# breakout-1.net
KiCad netlist of a schematic drawn in Altium Designer
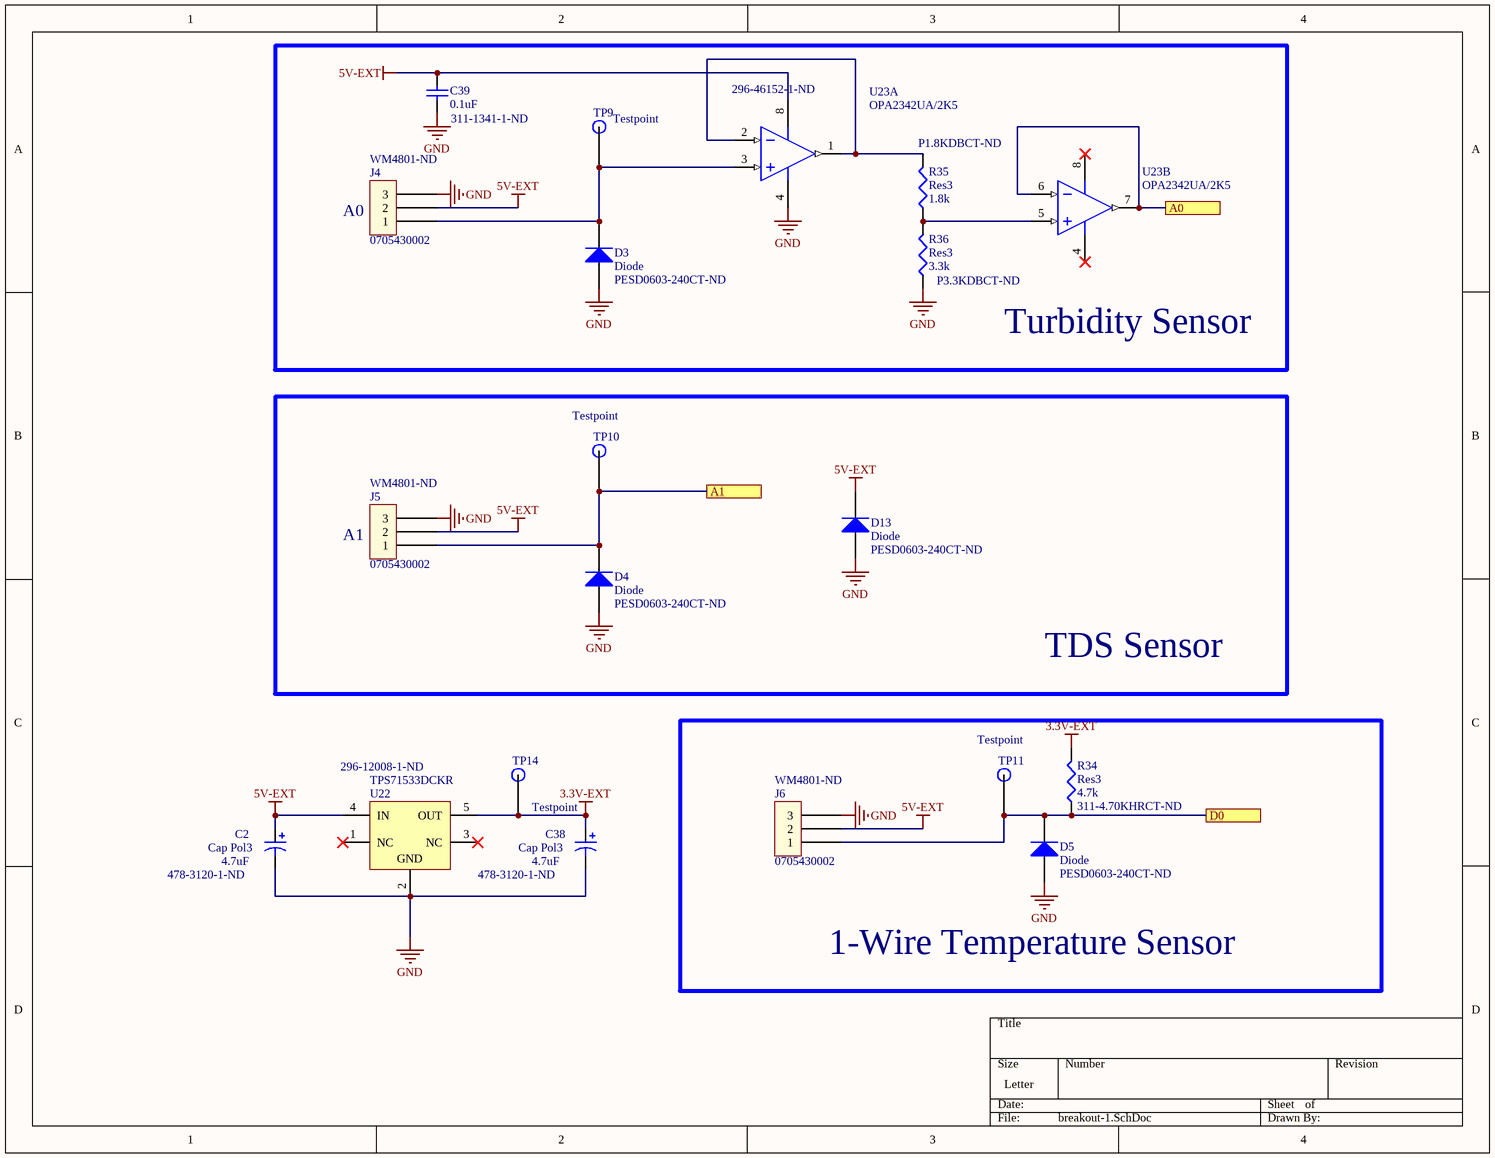
[diagram p0: breakout-1.SchDoc]

(export (version "E")
  (design (tool "Eeschema 10.0.6"))
  (components
    (comp (ref "C2")
      (value "Cap Pol3")
      (footprint "1206-pol")
      (description "Polarized Capacitor (Surface Mount)")
      (fields
        (field (name "ALTIUM_VALUE") "4.7uF")
        (field (name "SUPPLIER PART NUMBER 1") "478-3120-1-ND")
        (field (name "MANUFACTURER") "AVX Corporation")
        (field (name "MANUFACTURER PART NUMBER") "NOJA475M010RWJ")
      )
      (libsource (lib "Miscellaneous Devices") (part "Cap Pol3"))
    )
    (comp (ref "C38")
      (value "Cap Pol3")
      (footprint "1206-pol")
      (description "Polarized Capacitor (Surface Mount)")
      (fields
        (field (name "ALTIUM_VALUE") "4.7uF")
        (field (name "SUPPLIER PART NUMBER 1") "478-3120-1-ND")
        (field (name "MANUFACTURER") "AVX Corporation")
        (field (name "MANUFACTURER PART NUMBER") "NOJA475M010RWJ")
      )
      (libsource (lib "Miscellaneous Devices") (part "Cap Pol3"))
    )
    (comp (ref "C39")
      (value "0.1uF")
      (footprint "1608[0603]")
      (description "Capacitor (Semiconductor SIM Model)")
      (fields
        (field (name "SUPPLIER PART NUMBER 1") "311-1341-1-ND")
        (field (name "MANUFACTURER") "Yageo")
        (field (name "MANUFACTURER PART NUMBER") "CC0603KRX7R8BB104")
      )
      (libsource (lib "Miscellaneous Devices") (part "Cap Semi"))
    )
    (comp (ref "D3")
      (value "Diode")
      (footprint "J1-0603")
      (description "Default Diode")
      (fields
        (field (name "SUPPLIER PART NUMBER 1") "PESD0603-240CT-ND")
        (field (name "MANUFACTURER") "Littelfuse")
        (field (name "MANUFACTURER PART NUMBER") "RF1256-000")
        (field (name "PUBLISHER") "Altium Limited")
      )
      (libsource (lib "Miscellaneous Devices") (part "Diode"))
    )
    (comp (ref "D4")
      (value "Diode")
      (footprint "J1-0603")
      (description "Default Diode")
      (fields
        (field (name "SUPPLIER PART NUMBER 1") "PESD0603-240CT-ND")
        (field (name "MANUFACTURER") "Littelfuse")
        (field (name "MANUFACTURER PART NUMBER") "RF1256-000")
        (field (name "PUBLISHER") "Altium Limited")
      )
      (libsource (lib "Miscellaneous Devices") (part "Diode"))
    )
    (comp (ref "D5")
      (value "Diode")
      (footprint "J1-0603")
      (description "Default Diode")
      (fields
        (field (name "SUPPLIER PART NUMBER 1") "PESD0603-240CT-ND")
        (field (name "MANUFACTURER") "Littelfuse")
        (field (name "MANUFACTURER PART NUMBER") "RF1256-000")
        (field (name "PUBLISHER") "Altium Limited")
      )
      (libsource (lib "Miscellaneous Devices") (part "Diode"))
    )
    (comp (ref "D13")
      (value "Diode")
      (footprint "J1-0603")
      (description "Default Diode")
      (fields
        (field (name "SUPPLIER PART NUMBER 1") "PESD0603-240CT-ND")
        (field (name "MANUFACTURER") "Littelfuse")
        (field (name "MANUFACTURER PART NUMBER") "RF1256-000")
        (field (name "PUBLISHER") "Altium Limited")
      )
      (libsource (lib "Miscellaneous Devices") (part "Diode"))
    )
    (comp (ref "J4")
      (value "0705430002")
      (footprint "0705430002")
      (fields
        (field (name "SUPPLIER PART NUMBER 1") "WM4801-ND")
        (field (name "MANUFACTURER") "Molex")
        (field (name "MANUFACTURER PART NUMBER") "70543-0002")
      )
      (libsource (lib "molex") (part "0705430002"))
    )
    (comp (ref "J5")
      (value "0705430002")
      (footprint "0705430002")
      (fields
        (field (name "SUPPLIER PART NUMBER 1") "WM4801-ND")
        (field (name "MANUFACTURER") "Molex")
        (field (name "MANUFACTURER PART NUMBER") "70543-0002")
      )
      (libsource (lib "molex") (part "0705430002"))
    )
    (comp (ref "J6")
      (value "0705430002")
      (footprint "0705430002")
      (fields
        (field (name "SUPPLIER PART NUMBER 1") "WM4801-ND")
        (field (name "MANUFACTURER") "Molex")
        (field (name "MANUFACTURER PART NUMBER") "70543-0002")
      )
      (libsource (lib "molex") (part "0705430002"))
    )
    (comp (ref "R34")
      (value "Res3")
      (footprint "J1-0603")
      (description "Resistor")
      (fields
        (field (name "ALTIUM_VALUE") "4.7k")
        (field (name "SUPPLIER PART NUMBER 1") "311-4.70KHRCT-ND")
        (field (name "MANUFACTURER") "Yageo")
        (field (name "MANUFACTURER PART NUMBER") "RC0603FR-074K7L")
        (field (name "PUBLISHER") "Altium Limited")
      )
      (libsource (lib "Miscellaneous Devices") (part "Res3"))
    )
    (comp (ref "R35")
      (value "Res3")
      (footprint "J1-0603")
      (description "Resistor")
      (fields
        (field (name "ALTIUM_VALUE") "1.8k")
        (field (name "SUPPLIER PART NUMBER 1") "P1.8KDBCT-ND")
        (field (name "MANUFACTURER") "Panasonic")
        (field (name "MANUFACTURER PART NUMBER") "ERA3AEB182V")
        (field (name "PUBLISHER") "Altium Limited")
      )
      (libsource (lib "Miscellaneous Devices") (part "Res3"))
    )
    (comp (ref "R36")
      (value "Res3")
      (footprint "J1-0603")
      (description "Resistor")
      (fields
        (field (name "ALTIUM_VALUE") "3.3k")
        (field (name "SUPPLIER PART NUMBER 1") "P3.3KDBCT-ND")
        (field (name "MANUFACTURER") "Panasonic")
        (field (name "MANUFACTURER PART NUMBER") "ERA-3AEB332V")
        (field (name "PUBLISHER") "Altium Limited")
      )
      (libsource (lib "Miscellaneous Devices") (part "Res3"))
    )
    (comp (ref "TP9")
      (value "Testpoint")
      (footprint "testpoint")
      (description "SMT Testpoint")
      (libsource (lib "testpoints") (part "SMT Testpoint"))
    )
    (comp (ref "TP10")
      (value "Testpoint")
      (footprint "testpoint")
      (description "SMT Testpoint")
      (libsource (lib "testpoints") (part "SMT Testpoint"))
    )
    (comp (ref "TP11")
      (value "Testpoint")
      (footprint "testpoint")
      (description "SMT Testpoint")
      (libsource (lib "testpoints") (part "SMT Testpoint"))
    )
    (comp (ref "TP14")
      (value "Testpoint")
      (footprint "testpoint")
      (description "SMT Testpoint")
      (libsource (lib "testpoints") (part "SMT Testpoint"))
    )
    (comp (ref "U22")
      (value "TPS71533DCKR")
      (footprint "DCK0005A_L")
      (fields
        (field (name "MANUFACTURER") "Texas Instruments")
        (field (name "SUPPLIER PART NUMBER 1") "296-12008-1-ND")
      )
      (libsource (lib "Altium Content Vault") (part "TI-TPS71XXXX-XXDCK5"))
    )
    (comp (ref "U23")
      (value "OPA2342UA/2K5")
      (footprint "D0008A_M")
      (fields
        (field (name "MANUFACTURER") "Texas Instruments")
        (field (name "SUPPLIER PART NUMBER 1") "296-46152-1-ND")
      )
      (libsource (lib "Altium Content Vault") (part "TI-OPA-8_2"))
    )
  )
  (nets
    (net (code "1") (name "/A0") (class "Default")
      (node (ref "U23") (pin "6") (pinfunction "IN_B-_6") (pintype "input"))
      (node (ref "U23") (pin "7") (pinfunction "OUT_B_7") (pintype "output"))
    )
    (net (code "2") (name "/A1") (class "Default")
      (node (ref "D4") (pin "2") (pinfunction "K_2") (pintype "passive"))
      (node (ref "J5") (pin "1") (pinfunction "1_1") (pintype "passive"))
      (node (ref "TP10") (pin "1") (pinfunction "1_1") (pintype "passive"))
    )
    (net (code "3") (name "/D0") (class "Default")
      (node (ref "D5") (pin "2") (pinfunction "K_2") (pintype "passive"))
      (node (ref "J6") (pin "1") (pinfunction "1_1") (pintype "passive"))
      (node (ref "R34") (pin "1") (pinfunction "1_1") (pintype "passive"))
      (node (ref "TP11") (pin "1") (pinfunction "1_1") (pintype "passive"))
    )
    (net (code "4") (name "3.3V-EXT") (class "Default")
      (node (ref "C38") (pin "1") (pinfunction "1_1") (pintype "passive"))
      (node (ref "R34") (pin "2") (pinfunction "2_2") (pintype "passive"))
      (node (ref "TP14") (pin "1") (pinfunction "1_1") (pintype "passive"))
      (node (ref "U22") (pin "5") (pinfunction "OUT_5") (pintype "power_in"))
    )
    (net (code "5") (name "5V-EXT") (class "Default")
      (node (ref "C2") (pin "1") (pinfunction "1_1") (pintype "passive"))
      (node (ref "C39") (pin "1") (pinfunction "1_1") (pintype "passive"))
      (node (ref "D13") (pin "2") (pinfunction "K_2") (pintype "passive"))
      (node (ref "J4") (pin "2") (pinfunction "2_2") (pintype "passive"))
      (node (ref "J5") (pin "2") (pinfunction "2_2") (pintype "passive"))
      (node (ref "J6") (pin "2") (pinfunction "2_2") (pintype "passive"))
      (node (ref "U22") (pin "4") (pinfunction "IN_4") (pintype "power_in"))
      (node (ref "U23") (pin "8") (pinfunction "V+_8") (pintype "power_in"))
    )
    (net (code "6") (name "GND") (class "Default")
      (node (ref "C2") (pin "2") (pinfunction "2_2") (pintype "passive"))
      (node (ref "C38") (pin "2") (pinfunction "2_2") (pintype "passive"))
      (node (ref "C39") (pin "2") (pinfunction "2_2") (pintype "passive"))
      (node (ref "D13") (pin "1") (pinfunction "A_1") (pintype "passive"))
      (node (ref "D3") (pin "1") (pinfunction "A_1") (pintype "passive"))
      (node (ref "D4") (pin "1") (pinfunction "A_1") (pintype "passive"))
      (node (ref "D5") (pin "1") (pinfunction "A_1") (pintype "passive"))
      (node (ref "J4") (pin "3") (pinfunction "3_3") (pintype "passive"))
      (node (ref "J5") (pin "3") (pinfunction "3_3") (pintype "passive"))
      (node (ref "J6") (pin "3") (pinfunction "3_3") (pintype "passive"))
      (node (ref "R36") (pin "1") (pinfunction "1_1") (pintype "passive"))
      (node (ref "U22") (pin "2") (pinfunction "GND_2") (pintype "power_in"))
      (node (ref "U23") (pin "4") (pinfunction "V-_4") (pintype "power_in"))
    )
    (net (code "7") (name "Net-(D3-K)") (class "Default")
      (node (ref "D3") (pin "2") (pinfunction "K_2") (pintype "passive"))
      (node (ref "J4") (pin "1") (pinfunction "1_1") (pintype "passive"))
      (node (ref "TP9") (pin "1") (pinfunction "1_1") (pintype "passive"))
      (node (ref "U23") (pin "3") (pinfunction "IN_A+_3") (pintype "input"))
    )
    (net (code "8") (name "Net-(U23A-IN_A-)") (class "Default")
      (node (ref "R35") (pin "2") (pinfunction "2_2") (pintype "passive"))
      (node (ref "U23") (pin "1") (pinfunction "OUT_A_1") (pintype "output"))
      (node (ref "U23") (pin "2") (pinfunction "IN_A-_2") (pintype "input"))
    )
    (net (code "9") (name "Net-(U23B-IN_B+)") (class "Default")
      (node (ref "R35") (pin "1") (pinfunction "1_1") (pintype "passive"))
      (node (ref "R36") (pin "2") (pinfunction "2_2") (pintype "passive"))
      (node (ref "U23") (pin "5") (pinfunction "IN_B+_5") (pintype "input"))
    )
    (net (code "10") (name "unconnected-(U22-NC-Pad1)") (class "Default")
      (node (ref "U22") (pin "1") (pinfunction "NC_1") (pintype "passive+no_connect"))
    )
    (net (code "11") (name "unconnected-(U22-NC-Pad3)") (class "Default")
      (node (ref "U22") (pin "3") (pinfunction "NC_3") (pintype "passive+no_connect"))
    )
    (net (code "12") (name "unconnected-(U23B-V+-Pad8)") (class "Default")
      (node (ref "U23") (pin "8") (pinfunction "V+_8") (pintype "power_in+no_connect"))
    )
    (net (code "13") (name "unconnected-(U23B-V--Pad4)") (class "Default")
      (node (ref "U23") (pin "4") (pinfunction "V-_4") (pintype "power_in+no_connect"))
    )
  )
)
